# schema.net
KiCad netlist of a schematic drawn in EAGLE
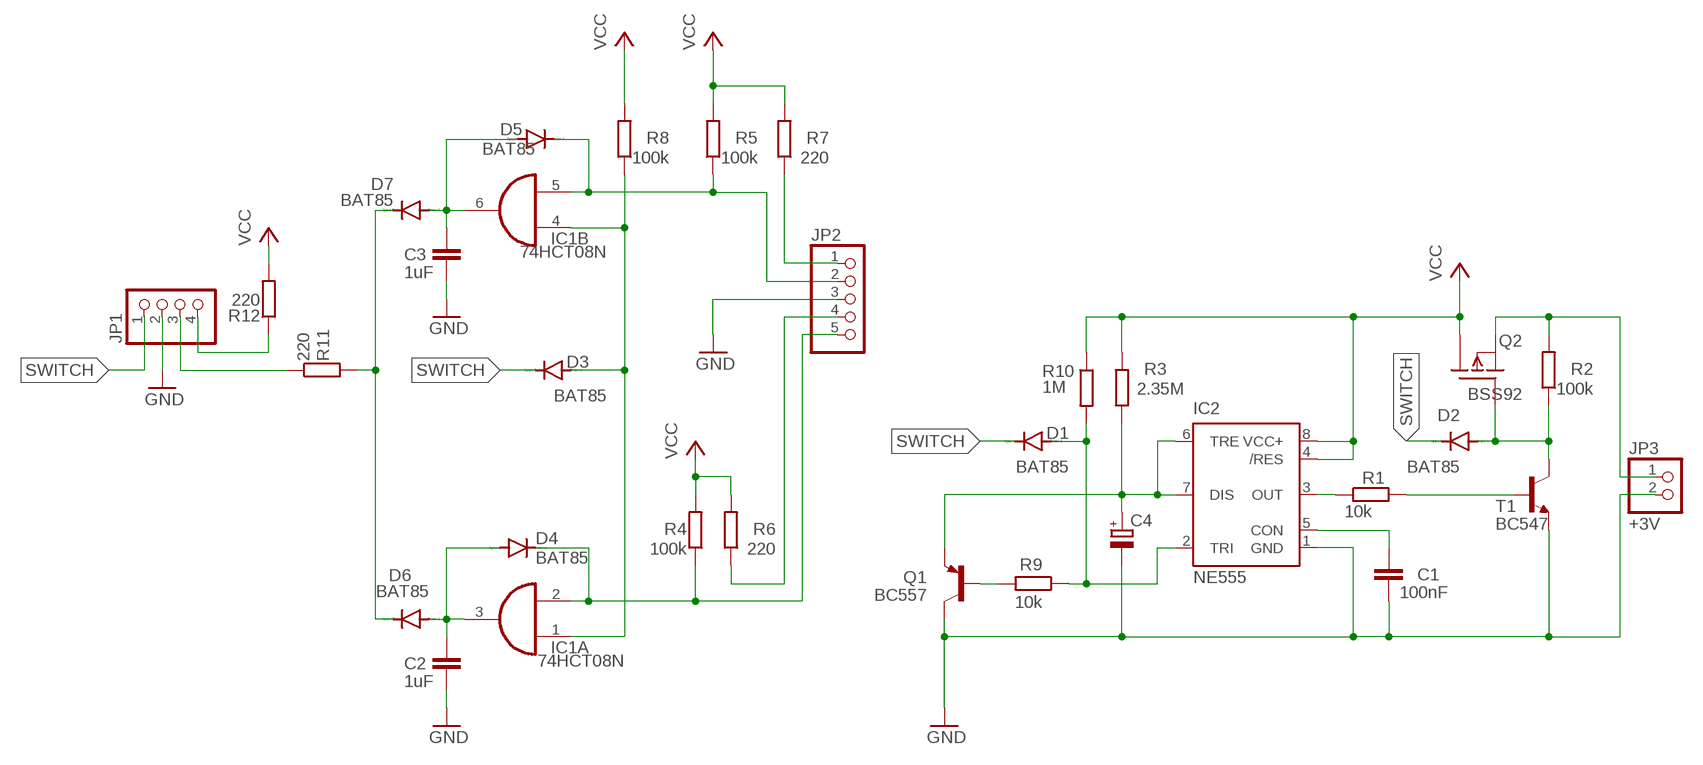
[diagram p0: schematic, sheet 1]
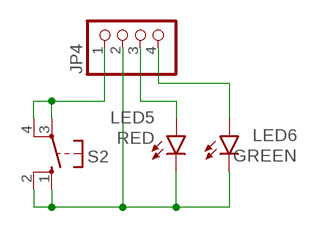
[diagram p1: schematic, sheet 2]
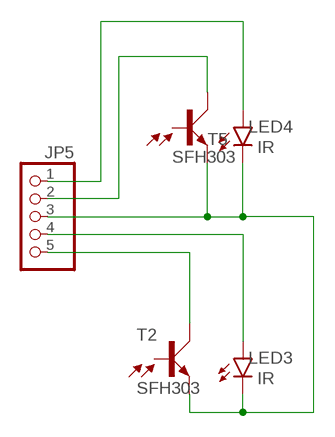
[diagram p2: schematic, sheet 3]

(export (version "E")
  (design (tool "Eeschema 10.0.6"))
  (components
    (comp (ref "C1")
      (value "100nF")
      (footprint "eagle-import:C025-024X044")
      (libsource (lib "eagle-import") (part "C-EU025-024X044"))
    )
    (comp (ref "C2")
      (value "1uF")
      (footprint "eagle-import:C025-024X044")
      (libsource (lib "eagle-import") (part "C-EU025-024X044"))
    )
    (comp (ref "C3")
      (value "1uF")
      (footprint "eagle-import:C025-024X044")
      (libsource (lib "eagle-import") (part "C-EU025-024X044"))
    )
    (comp (ref "C4")
      (value "CPOL-EUE2,5-6E")
      (footprint "eagle-import:E2,5-6E")
      (libsource (lib "eagle-import") (part "CPOL-EUE2,5-6E"))
    )
    (comp (ref "D1")
      (value "BAT85")
      (footprint "eagle-import:DO34-7")
      (libsource (lib "eagle-import") (part "BAT81"))
    )
    (comp (ref "D2")
      (value "BAT85")
      (footprint "eagle-import:DO34-7")
      (libsource (lib "eagle-import") (part "BAT81"))
    )
    (comp (ref "D3")
      (value "BAT85")
      (footprint "eagle-import:DO34-7")
      (libsource (lib "eagle-import") (part "BAT81"))
    )
    (comp (ref "D4")
      (value "BAT85")
      (footprint "eagle-import:DO34-7")
      (libsource (lib "eagle-import") (part "BAT81"))
    )
    (comp (ref "D5")
      (value "BAT85")
      (footprint "eagle-import:DO34-7")
      (libsource (lib "eagle-import") (part "BAT81"))
    )
    (comp (ref "D6")
      (value "BAT85")
      (footprint "eagle-import:DO34-7")
      (libsource (lib "eagle-import") (part "BAT81"))
    )
    (comp (ref "D7")
      (value "BAT85")
      (footprint "eagle-import:DO34-7")
      (libsource (lib "eagle-import") (part "BAT81"))
    )
    (comp (ref "IC1")
      (value "74HCT08N")
      (footprint "eagle-import:DIL14")
      (libsource (lib "eagle-import") (part "7408NHCT"))
    )
    (comp (ref "IC2")
      (value "NE555")
      (footprint "eagle-import:DIL-08")
      (fields (field (name "MF") "Arrow Electronics") (field (name "MPN") "NE555N"))
      (libsource (lib "eagle-import") (part "NE555"))
    )
    (comp (ref "JP1")
      (value "PINHD-1X4")
      (footprint "eagle-import:1X04")
      (libsource (lib "eagle-import") (part "PINHD-1X4"))
    )
    (comp (ref "JP2")
      (value "PINHD-1X5")
      (footprint "eagle-import:1X05")
      (libsource (lib "eagle-import") (part "PINHD-1X5"))
    )
    (comp (ref "JP3")
      (value "+3V")
      (footprint "eagle-import:1X02_90")
      (libsource (lib "eagle-import") (part "PINHD-1X2/90"))
    )
    (comp (ref "Q1")
      (value "BC557")
      (footprint "eagle-import:TO92")
      (libsource (lib "eagle-import") (part "BC557"))
    )
    (comp (ref "Q2")
      (value "BSS92")
      (footprint "eagle-import:TO92")
      (libsource (lib "eagle-import") (part "BSS92"))
    )
    (comp (ref "R1")
      (value "10k")
      (footprint "eagle-import:0204_7")
      (libsource (lib "eagle-import") (part "R-EU_0204/7"))
    )
    (comp (ref "R2")
      (value "100k")
      (footprint "eagle-import:0204_7")
      (libsource (lib "eagle-import") (part "R-EU_0204/7"))
    )
    (comp (ref "R3")
      (value "2.35M")
      (footprint "eagle-import:0204_7")
      (libsource (lib "eagle-import") (part "R-EU_0204/7"))
    )
    (comp (ref "R4")
      (value "100k")
      (footprint "eagle-import:0204_7")
      (libsource (lib "eagle-import") (part "R-EU_0204/7"))
    )
    (comp (ref "R5")
      (value "100k")
      (footprint "eagle-import:0204_7")
      (libsource (lib "eagle-import") (part "R-EU_0204/7"))
    )
    (comp (ref "R6")
      (value "220")
      (footprint "eagle-import:0204_7")
      (libsource (lib "eagle-import") (part "R-EU_0204/7"))
    )
    (comp (ref "R7")
      (value "220")
      (footprint "eagle-import:0204_7")
      (libsource (lib "eagle-import") (part "R-EU_0204/7"))
    )
    (comp (ref "R8")
      (value "100k")
      (footprint "eagle-import:0204_7")
      (libsource (lib "eagle-import") (part "R-EU_0204/7"))
    )
    (comp (ref "R9")
      (value "10k")
      (footprint "eagle-import:0204_7")
      (libsource (lib "eagle-import") (part "R-EU_0204/7"))
    )
    (comp (ref "R10")
      (value "1M")
      (footprint "eagle-import:0204_7")
      (libsource (lib "eagle-import") (part "R-EU_0204/7"))
    )
    (comp (ref "R11")
      (value "220")
      (footprint "eagle-import:0204_7")
      (libsource (lib "eagle-import") (part "R-EU_0204/7"))
    )
    (comp (ref "R12")
      (value "220")
      (footprint "eagle-import:0204_7")
      (libsource (lib "eagle-import") (part "R-EU_0204/7"))
    )
    (comp (ref "T1")
      (value "BC547")
      (footprint "eagle-import:TO92")
      (libsource (lib "eagle-import") (part "BC547"))
    )
    (comp (ref "JP5")
      (value "PINHD-1X5")
      (footprint "eagle-import:1X05")
      (libsource (lib "eagle-import") (part "PINHD-1X5"))
    )
    (comp (ref "LED3")
      (value "IR")
      (footprint "eagle-import:LED5MM")
      (libsource (lib "eagle-import") (part "LED5MM"))
    )
    (comp (ref "LED4")
      (value "IR")
      (footprint "eagle-import:LED5MM")
      (libsource (lib "eagle-import") (part "LED5MM"))
    )
    (comp (ref "T2")
      (value "SFH303")
      (footprint "eagle-import:SFH303")
      (libsource (lib "eagle-import") (part "SFH303"))
    )
    (comp (ref "T5")
      (value "SFH303")
      (footprint "eagle-import:SFH303")
      (libsource (lib "eagle-import") (part "SFH303"))
    )
    (comp (ref "JP4")
      (value "PINHD-1X4")
      (footprint "eagle-import:1X04")
      (libsource (lib "eagle-import") (part "PINHD-1X4"))
    )
    (comp (ref "LED5")
      (value "RED")
      (footprint "eagle-import:LED5MM")
      (libsource (lib "eagle-import") (part "LED5MM"))
    )
    (comp (ref "LED6")
      (value "GREEN")
      (footprint "eagle-import:LED5MM")
      (libsource (lib "eagle-import") (part "LED5MM"))
    )
    (comp (ref "S2")
      (value "10-XX")
      (footprint "eagle-import:B3F-10XX")
      (fields (field (name "MPN") "B3F-1000"))
      (libsource (lib "eagle-import") (part "10-XX"))
    )
  )
  (nets
    (net (code "1") (name "GND") (class "Default")
      (node (ref "C1") (pin "2") (pinfunction "2_2") (pintype "passive"))
      (node (ref "C2") (pin "2") (pinfunction "2_2") (pintype "passive"))
      (node (ref "C3") (pin "2") (pinfunction "2_2") (pintype "passive"))
      (node (ref "C4") (pin "-") (pinfunction "-_-") (pintype "passive"))
      (node (ref "IC2") (pin "1") (pinfunction "GND_1") (pintype "power_in"))
      (node (ref "JP1") (pin "2") (pinfunction "2_2") (pintype "passive"))
      (node (ref "JP2") (pin "3") (pinfunction "3_3") (pintype "passive"))
      (node (ref "JP3") (pin "2") (pinfunction "2_2") (pintype "passive"))
      (node (ref "Q1") (pin "3") (pinfunction "C_3") (pintype "passive"))
      (node (ref "T1") (pin "1") (pinfunction "E_1") (pintype "passive"))
    )
    (net (code "2") (name "Net-(D6-PadC)") (class "Default")
      (node (ref "D6") (pin "C") (pinfunction "C_C") (pintype "passive"))
      (node (ref "D7") (pin "C") (pinfunction "C_C") (pintype "passive"))
      (node (ref "R11") (pin "2") (pinfunction "2_2") (pintype "passive"))
    )
    (net (code "3") (name "Net-(IC1A-I0)") (class "Default")
      (node (ref "D3") (pin "A") (pinfunction "A_A") (pintype "passive"))
      (node (ref "IC1") (pin "1") (pinfunction "I0_1") (pintype "input"))
      (node (ref "IC1") (pin "4") (pinfunction "I0_4") (pintype "input"))
      (node (ref "R8") (pin "1") (pinfunction "1_1") (pintype "passive"))
    )
    (net (code "4") (name "Net-(IC1A-I1)") (class "Default")
      (node (ref "D4") (pin "C") (pinfunction "C_C") (pintype "passive"))
      (node (ref "IC1") (pin "2") (pinfunction "I1_2") (pintype "input"))
      (node (ref "JP2") (pin "5") (pinfunction "5_5") (pintype "passive"))
      (node (ref "R4") (pin "1") (pinfunction "1_1") (pintype "passive"))
    )
    (net (code "5") (name "Net-(IC1A-O)") (class "Default")
      (node (ref "C2") (pin "1") (pinfunction "1_1") (pintype "passive"))
      (node (ref "D4") (pin "A") (pinfunction "A_A") (pintype "passive"))
      (node (ref "D6") (pin "A") (pinfunction "A_A") (pintype "passive"))
      (node (ref "IC1") (pin "3") (pinfunction "O_3") (pintype "output"))
    )
    (net (code "6") (name "Net-(IC1B-I1)") (class "Default")
      (node (ref "D5") (pin "C") (pinfunction "C_C") (pintype "passive"))
      (node (ref "IC1") (pin "5") (pinfunction "I1_5") (pintype "input"))
      (node (ref "JP2") (pin "2") (pinfunction "2_2") (pintype "passive"))
      (node (ref "R5") (pin "1") (pinfunction "1_1") (pintype "passive"))
    )
    (net (code "7") (name "Net-(IC1B-O)") (class "Default")
      (node (ref "C3") (pin "1") (pinfunction "1_1") (pintype "passive"))
      (node (ref "D5") (pin "A") (pinfunction "A_A") (pintype "passive"))
      (node (ref "D7") (pin "A") (pinfunction "A_A") (pintype "passive"))
      (node (ref "IC1") (pin "6") (pinfunction "O_6") (pintype "output"))
    )
    (net (code "8") (name "Net-(IC2-CON)") (class "Default")
      (node (ref "C1") (pin "1") (pinfunction "1_1") (pintype "passive"))
      (node (ref "IC2") (pin "5") (pinfunction "CON_5") (pintype "input"))
    )
    (net (code "9") (name "Net-(IC2-DIS)") (class "Default")
      (node (ref "C4") (pin "+") (pinfunction "+_+") (pintype "passive"))
      (node (ref "IC2") (pin "6") (pinfunction "TRE_6") (pintype "input"))
      (node (ref "IC2") (pin "7") (pinfunction "DIS_7") (pintype "input"))
      (node (ref "Q1") (pin "1") (pinfunction "E_1") (pintype "passive"))
      (node (ref "R3") (pin "1") (pinfunction "1_1") (pintype "passive"))
    )
    (net (code "10") (name "Net-(IC2-OUT)") (class "Default")
      (node (ref "IC2") (pin "3") (pinfunction "OUT_3") (pintype "output"))
      (node (ref "R1") (pin "1") (pinfunction "1_1") (pintype "passive"))
    )
    (net (code "11") (name "Net-(IC2-TRI)") (class "Default")
      (node (ref "D1") (pin "A") (pinfunction "A_A") (pintype "passive"))
      (node (ref "IC2") (pin "2") (pinfunction "TRI_2") (pintype "input"))
      (node (ref "R10") (pin "2") (pinfunction "2_2") (pintype "passive"))
      (node (ref "R9") (pin "1") (pinfunction "1_1") (pintype "passive"))
    )
    (net (code "12") (name "Net-(JP1-Pad3)") (class "Default")
      (node (ref "JP1") (pin "3") (pinfunction "3_3") (pintype "passive"))
      (node (ref "R11") (pin "1") (pinfunction "1_1") (pintype "passive"))
    )
    (net (code "13") (name "Net-(JP1-Pad4)") (class "Default")
      (node (ref "JP1") (pin "4") (pinfunction "4_4") (pintype "passive"))
      (node (ref "R12") (pin "1") (pinfunction "1_1") (pintype "passive"))
    )
    (net (code "14") (name "Net-(JP2-Pad1)") (class "Default")
      (node (ref "JP2") (pin "1") (pinfunction "1_1") (pintype "passive"))
      (node (ref "R7") (pin "1") (pinfunction "1_1") (pintype "passive"))
    )
    (net (code "15") (name "Net-(JP2-Pad4)") (class "Default")
      (node (ref "JP2") (pin "4") (pinfunction "4_4") (pintype "passive"))
      (node (ref "R6") (pin "1") (pinfunction "1_1") (pintype "passive"))
    )
    (net (code "16") (name "Net-(JP4-Pad3)") (class "Default")
      (node (ref "JP4") (pin "3") (pinfunction "3_3") (pintype "passive"))
      (node (ref "LED5") (pin "A") (pinfunction "A_A") (pintype "passive"))
    )
    (net (code "17") (name "Net-(JP4-Pad4)") (class "Default")
      (node (ref "JP4") (pin "4") (pinfunction "4_4") (pintype "passive"))
      (node (ref "LED6") (pin "A") (pinfunction "A_A") (pintype "passive"))
    )
    (net (code "18") (name "Net-(JP5-Pad1)") (class "Default")
      (node (ref "JP5") (pin "1") (pinfunction "1_1") (pintype "passive"))
      (node (ref "LED4") (pin "A") (pinfunction "A_A") (pintype "passive"))
    )
    (net (code "19") (name "Net-(JP5-Pad4)") (class "Default")
      (node (ref "JP5") (pin "4") (pinfunction "4_4") (pintype "passive"))
      (node (ref "LED3") (pin "A") (pinfunction "A_A") (pintype "passive"))
    )
    (net (code "20") (name "Net-(LED3-C)") (class "Default")
      (node (ref "JP5") (pin "3") (pinfunction "3_3") (pintype "passive"))
      (node (ref "LED3") (pin "K") (pinfunction "C_K") (pintype "passive"))
      (node (ref "LED4") (pin "K") (pinfunction "C_K") (pintype "passive"))
      (node (ref "T2") (pin "1") (pinfunction "E_1") (pintype "passive"))
      (node (ref "T5") (pin "1") (pinfunction "E_1") (pintype "passive"))
    )
    (net (code "21") (name "Net-(LED5-C)") (class "Default")
      (node (ref "JP4") (pin "2") (pinfunction "2_2") (pintype "passive"))
      (node (ref "LED5") (pin "K") (pinfunction "C_K") (pintype "passive"))
      (node (ref "LED6") (pin "K") (pinfunction "C_K") (pintype "passive"))
      (node (ref "S2") (pin "1") (pinfunction "S_1") (pintype "passive"))
      (node (ref "S2") (pin "2") (pinfunction "S1_2") (pintype "passive"))
    )
    (net (code "22") (name "Net-(Q1-B)") (class "Default")
      (node (ref "Q1") (pin "2") (pinfunction "B_2") (pintype "passive"))
      (node (ref "R9") (pin "2") (pinfunction "2_2") (pintype "passive"))
    )
    (net (code "23") (name "Net-(Q2-G)") (class "Default")
      (node (ref "D2") (pin "A") (pinfunction "A_A") (pintype "passive"))
      (node (ref "Q2") (pin "1") (pinfunction "G_1") (pintype "passive"))
      (node (ref "R2") (pin "1") (pinfunction "1_1") (pintype "passive"))
      (node (ref "T1") (pin "3") (pinfunction "C_3") (pintype "passive"))
    )
    (net (code "24") (name "Net-(Q2-S)") (class "Default")
      (node (ref "JP3") (pin "1") (pinfunction "1_1") (pintype "passive"))
      (node (ref "Q2") (pin "3") (pinfunction "S_3") (pintype "passive"))
      (node (ref "R2") (pin "2") (pinfunction "2_2") (pintype "passive"))
    )
    (net (code "25") (name "Net-(S2-P)") (class "Default")
      (node (ref "JP4") (pin "1") (pinfunction "1_1") (pintype "passive"))
      (node (ref "S2") (pin "3") (pinfunction "P_3") (pintype "passive"))
      (node (ref "S2") (pin "4") (pinfunction "P1_4") (pintype "passive"))
    )
    (net (code "26") (name "Net-(T1-B)") (class "Default")
      (node (ref "R1") (pin "2") (pinfunction "2_2") (pintype "passive"))
      (node (ref "T1") (pin "2") (pinfunction "B_2") (pintype "passive"))
    )
    (net (code "27") (name "Net-(T2-C)") (class "Default")
      (node (ref "JP5") (pin "5") (pinfunction "5_5") (pintype "passive"))
      (node (ref "T2") (pin "2") (pinfunction "C_2") (pintype "passive"))
    )
    (net (code "28") (name "Net-(T5-C)") (class "Default")
      (node (ref "JP5") (pin "2") (pinfunction "2_2") (pintype "passive"))
      (node (ref "T5") (pin "2") (pinfunction "C_2") (pintype "passive"))
    )
    (net (code "29") (name "SWITCH") (class "Default")
      (node (ref "D1") (pin "C") (pinfunction "C_C") (pintype "passive"))
      (node (ref "D2") (pin "C") (pinfunction "C_C") (pintype "passive"))
      (node (ref "D3") (pin "C") (pinfunction "C_C") (pintype "passive"))
      (node (ref "JP1") (pin "1") (pinfunction "1_1") (pintype "passive"))
    )
    (net (code "30") (name "VCC") (class "Default")
      (node (ref "IC2") (pin "4") (pinfunction "/RES_4") (pintype "input"))
      (node (ref "IC2") (pin "8") (pinfunction "VCC+_8") (pintype "power_in"))
      (node (ref "Q2") (pin "2") (pinfunction "D_2") (pintype "passive"))
      (node (ref "R10") (pin "1") (pinfunction "1_1") (pintype "passive"))
      (node (ref "R12") (pin "2") (pinfunction "2_2") (pintype "passive"))
      (node (ref "R3") (pin "2") (pinfunction "2_2") (pintype "passive"))
      (node (ref "R4") (pin "2") (pinfunction "2_2") (pintype "passive"))
      (node (ref "R5") (pin "2") (pinfunction "2_2") (pintype "passive"))
      (node (ref "R6") (pin "2") (pinfunction "2_2") (pintype "passive"))
      (node (ref "R7") (pin "2") (pinfunction "2_2") (pintype "passive"))
      (node (ref "R8") (pin "2") (pinfunction "2_2") (pintype "passive"))
    )
    (net (code "31") (name "unconnected-(T2-B-Pad3)") (class "Default")
      (node (ref "T2") (pin "3") (pinfunction "B_3") (pintype "passive"))
    )
    (net (code "32") (name "unconnected-(T5-B-Pad3)") (class "Default")
      (node (ref "T5") (pin "3") (pinfunction "B_3") (pintype "passive"))
    )
  )
)
